# USB.net
KiCad netlist of a schematic drawn in Altium Designer
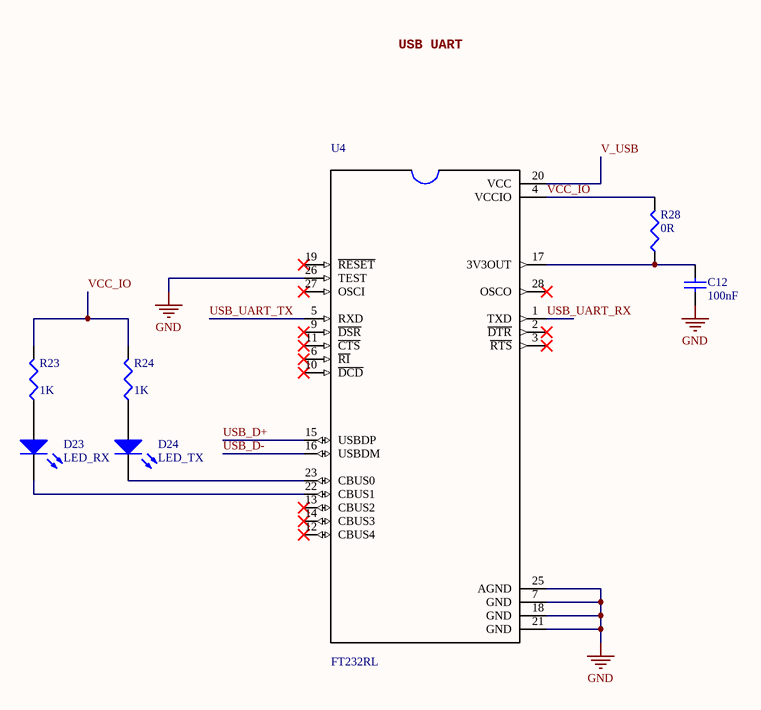
[diagram p0: USB.SchDoc]

(export (version "E")
  (design (tool "Eeschema 10.0.6"))
  (components
    (comp (ref "C12")
      (value "100nF")
      (footprint "1608[0603]")
      (description "CAP CER 0.1UF 16V X7R 0603")
      (fields
        (field (name "DIGI-KEY PART NUMBER") "478-7617-1-ND")
        (field (name "MANUFACTURER") "AVX Corporation")
      )
      (libsource (lib "Miscellaneous Devices") (part "Cap"))
    )
    (comp (ref "D23")
      (value "LED_RX")
      (footprint "1608[0603]")
      (description "LED RED DIFFUSED 0603 SMD")
      (fields
        (field (name "DIGI-KEY PART NUMBER") "475-1195-1-ND")
        (field (name "MANUFACTURER") "OSRAM Opto Semiconductors Inc.")
      )
      (libsource (lib "Miscellaneous Devices") (part "LED2"))
    )
    (comp (ref "D24")
      (value "LED_TX")
      (footprint "1608[0603]")
      (description "LED YELLOW DIFFUSED 0603 SMD")
      (fields
        (field (name "DIGI-KEY PART NUMBER") "475-1196-1-ND")
        (field (name "MANUFACTURER") "OSRAM Opto Semiconductors Inc.")
      )
      (libsource (lib "Miscellaneous Devices") (part "LED2"))
    )
    (comp (ref "R23")
      (value "1K")
      (footprint "1608[0603]")
      (description "RES SMD 1K OHM 0.1% 1/10W 0603")
      (fields (field (name "DIGI-KEY PART NUMBER") "YAG1237CT-ND") (field (name "MANUFACTURER") "Yageo"))
      (libsource (lib "Miscellaneous Devices") (part "Res3"))
    )
    (comp (ref "R24")
      (value "1K")
      (footprint "1608[0603]")
      (description "RES SMD 1K OHM 0.1% 1/10W 0603")
      (fields (field (name "DIGI-KEY PART NUMBER") "YAG1237CT-ND") (field (name "MANUFACTURER") "Yageo"))
      (libsource (lib "Miscellaneous Devices") (part "Res3"))
    )
    (comp (ref "R28")
      (value "0R")
      (footprint "1608[0603]")
      (description "RES 0 OHM JUMPER 1/8W 0603")
      (fields
        (field (name "DIGI-KEY PART NUMBER") "749-1745-1-ND")
        (field (name "MANUFACTURER") "Vishay Beyschlag")
      )
      (libsource (lib "Miscellaneous Devices") (part "Res3"))
    )
    (comp (ref "U4")
      (value "FT232RL")
      (footprint "SOP65P780X200-28N")
      (description "USB Bridge, USB to UART USB 2.0 UART Interface 28-SSOP")
      (fields
        (field (name "DIGI-KEY PART NUMBER") "768-1007-1-ND")
        (field (name "MANUFACTURER") "FTDI, Future Technology Devices International Ltd")
      )
      (libsource (lib "FT232RL-REEL") (part "FT232RL-REEL"))
    )
  )
  (nets
    (net (code "1") (name "/USB_D+") (class "Default")
      (node (ref "U4") (pin "15") (pinfunction "USBDP_15") (pintype "bidirectional"))
    )
    (net (code "2") (name "/USB_D-") (class "Default")
      (node (ref "U4") (pin "16") (pinfunction "USBDM_16") (pintype "bidirectional"))
    )
    (net (code "3") (name "/USB_UART_RX") (class "Default")
      (node (ref "U4") (pin "1") (pinfunction "TXD_1") (pintype "output"))
    )
    (net (code "4") (name "/USB_UART_TX") (class "Default")
      (node (ref "U4") (pin "5") (pinfunction "RXD_5") (pintype "input"))
    )
    (net (code "5") (name "/VCC_IO") (class "Default")
      (node (ref "R23") (pin "2") (pinfunction "2_2") (pintype "passive"))
      (node (ref "R24") (pin "2") (pinfunction "2_2") (pintype "passive"))
      (node (ref "R28") (pin "2") (pinfunction "2_2") (pintype "passive"))
      (node (ref "U4") (pin "4") (pinfunction "VCCIO_4") (pintype "power_in"))
    )
    (net (code "6") (name "/V_USB") (class "Default")
      (node (ref "U4") (pin "20") (pinfunction "VCC_20") (pintype "power_in"))
    )
    (net (code "7") (name "GND") (class "Default")
      (node (ref "C12") (pin "2") (pinfunction "2_2") (pintype "passive"))
      (node (ref "U4") (pin "18") (pinfunction "GND_18") (pintype "passive"))
      (node (ref "U4") (pin "21") (pinfunction "GND_21") (pintype "passive"))
      (node (ref "U4") (pin "25") (pinfunction "AGND_25") (pintype "passive"))
      (node (ref "U4") (pin "26") (pinfunction "TEST_26") (pintype "input"))
      (node (ref "U4") (pin "7") (pinfunction "GND_7") (pintype "passive"))
    )
    (net (code "8") (name "Net-(D23-A)") (class "Default")
      (node (ref "D23") (pin "1") (pinfunction "A_1") (pintype "passive"))
      (node (ref "R23") (pin "1") (pinfunction "1_1") (pintype "passive"))
    )
    (net (code "9") (name "Net-(D23-K)") (class "Default")
      (node (ref "D23") (pin "2") (pinfunction "K_2") (pintype "passive"))
      (node (ref "U4") (pin "22") (pinfunction "CBUS1_22") (pintype "bidirectional"))
    )
    (net (code "10") (name "Net-(D24-A)") (class "Default")
      (node (ref "D24") (pin "1") (pinfunction "A_1") (pintype "passive"))
      (node (ref "R24") (pin "1") (pinfunction "1_1") (pintype "passive"))
    )
    (net (code "11") (name "Net-(D24-K)") (class "Default")
      (node (ref "D24") (pin "2") (pinfunction "K_2") (pintype "passive"))
      (node (ref "U4") (pin "23") (pinfunction "CBUS0_23") (pintype "bidirectional"))
    )
    (net (code "12") (name "Net-(U4-3V3OUT)") (class "Default")
      (node (ref "C12") (pin "1") (pinfunction "1_1") (pintype "passive"))
      (node (ref "R28") (pin "1") (pinfunction "1_1") (pintype "passive"))
      (node (ref "U4") (pin "17") (pinfunction "3V3OUT_17") (pintype "output"))
    )
    (net (code "13") (name "unconnected-(U4-CBUS2-Pad13)") (class "Default")
      (node (ref "U4") (pin "13") (pinfunction "CBUS2_13") (pintype "bidirectional+no_connect"))
    )
    (net (code "14") (name "unconnected-(U4-CBUS3-Pad14)") (class "Default")
      (node (ref "U4") (pin "14") (pinfunction "CBUS3_14") (pintype "bidirectional+no_connect"))
    )
    (net (code "15") (name "unconnected-(U4-CBUS4-Pad12)") (class "Default")
      (node (ref "U4") (pin "12") (pinfunction "CBUS4_12") (pintype "bidirectional+no_connect"))
    )
    (net (code "16") (name "unconnected-(U4-OSCI-Pad27)") (class "Default")
      (node (ref "U4") (pin "27") (pinfunction "OSCI_27") (pintype "input+no_connect"))
    )
    (net (code "17") (name "unconnected-(U4-OSCO-Pad28)") (class "Default")
      (node (ref "U4") (pin "28") (pinfunction "OSCO_28") (pintype "output+no_connect"))
    )
    (net (code "18") (name "unconnected-(U4-~{CTS}-Pad11)") (class "Default")
      (node (ref "U4") (pin "11") (pinfunction "~{CTS}_11") (pintype "input+no_connect"))
    )
    (net (code "19") (name "unconnected-(U4-~{DCD}-Pad10)") (class "Default")
      (node (ref "U4") (pin "10") (pinfunction "~{DCD}_10") (pintype "input+no_connect"))
    )
    (net (code "20") (name "unconnected-(U4-~{DSR}-Pad9)") (class "Default")
      (node (ref "U4") (pin "9") (pinfunction "~{DSR}_9") (pintype "input+no_connect"))
    )
    (net (code "21") (name "unconnected-(U4-~{DTR}-Pad2)") (class "Default")
      (node (ref "U4") (pin "2") (pinfunction "~{DTR}_2") (pintype "output+no_connect"))
    )
    (net (code "22") (name "unconnected-(U4-~{RESET}-Pad19)") (class "Default")
      (node (ref "U4") (pin "19") (pinfunction "~{RESET}_19") (pintype "input+no_connect"))
    )
    (net (code "23") (name "unconnected-(U4-~{RI}-Pad6)") (class "Default")
      (node (ref "U4") (pin "6") (pinfunction "~{RI}_6") (pintype "input+no_connect"))
    )
    (net (code "24") (name "unconnected-(U4-~{RTS}-Pad3)") (class "Default")
      (node (ref "U4") (pin "3") (pinfunction "~{RTS}_3") (pintype "output+no_connect"))
    )
  )
)
